# USB_PROGRAMMER.net
KiCad netlist of a schematic drawn in Altium Designer
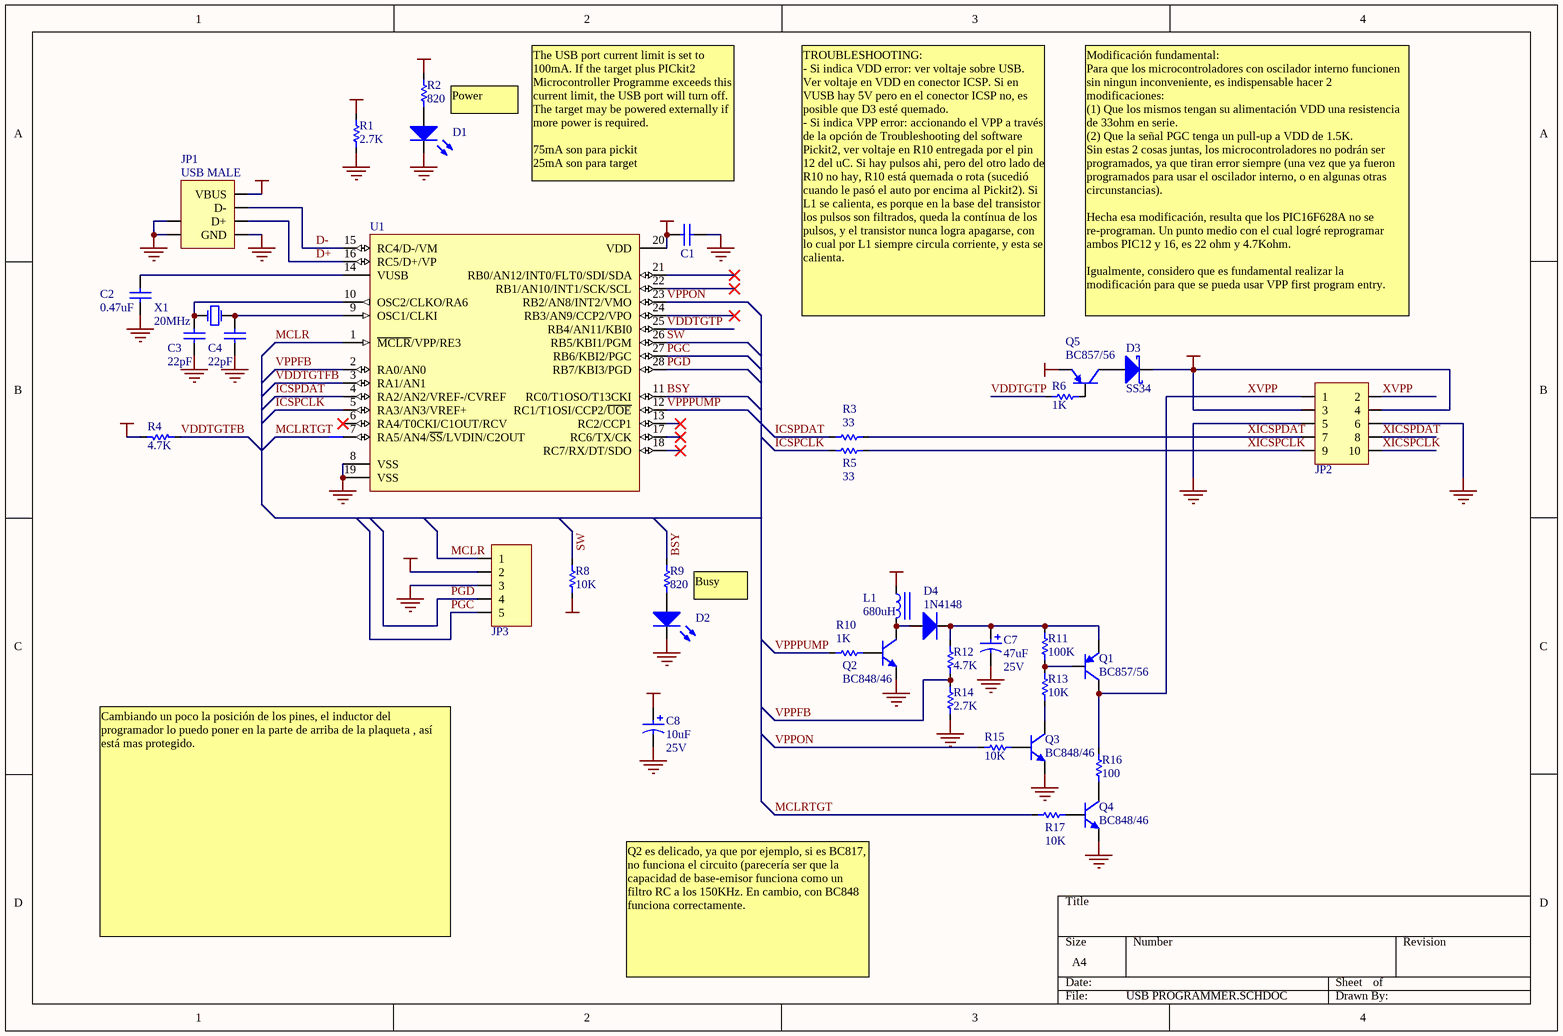
[diagram p0: USB PROGRAMMER.SCHDOC]

(export (version "E")
  (design (tool "Eeschema 10.0.6"))
  (components
    (comp (ref "C1")
      (value "Cap")
      (footprint "1206NP")
      (description "Capacitor")
      (fields (field (name "VOLTAGE") "50V"))
      (libsource (lib "FEDE") (part "Cap"))
    )
    (comp (ref "C2")
      (value "0.47uF")
      (footprint "1206NP")
      (description "Capacitor")
      (fields (field (name "VOLTAGE") "50V") (field (name "Comment") "Cap"))
      (libsource (lib "FEDE") (part "Cap"))
    )
    (comp (ref "C3")
      (value "22pF")
      (footprint "1206NP")
      (description "Capacitor")
      (fields (field (name "VOLTAGE") "50V") (field (name "Comment") "Cap"))
      (libsource (lib "FEDE") (part "Cap"))
    )
    (comp (ref "C4")
      (value "22pF")
      (footprint "1206NP")
      (description "Capacitor")
      (fields (field (name "VOLTAGE") "50V") (field (name "Comment") "Cap"))
      (libsource (lib "FEDE") (part "Cap"))
    )
    (comp (ref "C7")
      (value "47uF")
      (footprint "cap4mm")
      (description "Capacitor Polarizado")
      (fields (field (name "VOLTAJE") "25V") (field (name "Comment") "Cap Pol"))
      (libsource (lib "FEDE") (part "Cap Pol"))
    )
    (comp (ref "C8")
      (value "10uF")
      (footprint "cap4mm")
      (description "Capacitor Polarizado")
      (fields (field (name "VOLTAJE") "25V") (field (name "Comment") "Cap Pol"))
      (libsource (lib "FEDE") (part "Cap Pol"))
    )
    (comp (ref "D1")
      (value "LED")
      (footprint "LED3mm")
      (description "Led")
      (libsource (lib "FEDE") (part "LED"))
    )
    (comp (ref "D2")
      (value "LED")
      (footprint "LED3mm")
      (description "Led")
      (libsource (lib "FEDE") (part "LED"))
    )
    (comp (ref "D3")
      (value "SS34")
      (footprint "diode600")
      (description "Schottky Diode 3A 40V")
      (libsource (lib "FEDE") (part "1N5822"))
    )
    (comp (ref "D4")
      (value "1N4148")
      (footprint "DSMD1MM")
      (description "High Conductance Fast Diode")
      (libsource (lib "FEDE") (part "1N4148"))
    )
    (comp (ref "JP1")
      (value "USB MALE")
      (footprint "USB_A_MALE")
      (description "USB Connector")
      (libsource (lib "FEDE") (part "USB"))
    )
    (comp (ref "JP2")
      (value "Header5x1")
      (footprint "IDC5x2_90")
      (description "Header 5x2")
      (libsource (lib "FEDE") (part "Header5x2"))
    )
    (comp (ref "JP3")
      (value "Header5x1")
      (footprint "HDR5x1")
      (description "Header 5x1")
      (libsource (lib "FEDE") (part "Header5x1"))
    )
    (comp (ref "L1")
      (value "680uH")
      (footprint "RES400TH")
      (description "Inductor")
      (libsource (lib "FEDE") (part "Inductor"))
    )
    (comp (ref "Q1")
      (value "BC857/56")
      (footprint "SOT23")
      (description "100mA 65V PNP Bipolar Transistor")
      (libsource (lib "FEDE") (part "BC856A"))
    )
    (comp (ref "Q2")
      (value "BC848/46")
      (footprint "SOT23")
      (description "100mA 65V NPN Bipolar Transistor")
      (libsource (lib "FEDE") (part "BC846A"))
    )
    (comp (ref "Q3")
      (value "BC848/46")
      (footprint "SOT23")
      (description "100mA 65V NPN Bipolar Transistor")
      (libsource (lib "FEDE") (part "BC846A"))
    )
    (comp (ref "Q4")
      (value "BC848/46")
      (footprint "SOT23")
      (description "100mA 65V NPN Bipolar Transistor")
      (libsource (lib "FEDE") (part "BC846A"))
    )
    (comp (ref "Q5")
      (value "BC857/56")
      (footprint "SOT23")
      (description "100mA 65V PNP Bipolar Transistor")
      (libsource (lib "FEDE") (part "BC856A"))
    )
    (comp (ref "R1")
      (value "2.7K")
      (footprint "1206NP")
      (description "Resistor")
      (fields (field (name "POWER") "0.25W") (field (name "Comment") "Res"))
      (libsource (lib "FEDE") (part "Res"))
    )
    (comp (ref "R2")
      (value "820")
      (footprint "1206NP")
      (description "Resistor")
      (fields (field (name "POWER") "0.25W") (field (name "Comment") "Res"))
      (libsource (lib "FEDE") (part "Res"))
    )
    (comp (ref "R3")
      (value "33")
      (footprint "1206NP")
      (description "Resistor")
      (fields (field (name "POWER") "0.25W") (field (name "Comment") "Res"))
      (libsource (lib "FEDE") (part "Res"))
    )
    (comp (ref "R4")
      (value "4.7K")
      (footprint "1206NP")
      (description "Resistor")
      (fields (field (name "POWER") "0.25W") (field (name "Comment") "Res"))
      (libsource (lib "FEDE") (part "Res"))
    )
    (comp (ref "R5")
      (value "33")
      (footprint "1206NP")
      (description "Resistor")
      (fields (field (name "POWER") "0.25W") (field (name "Comment") "Res"))
      (libsource (lib "FEDE") (part "Res"))
    )
    (comp (ref "R6")
      (value "1K")
      (footprint "res250th_vertical")
      (description "Resistor")
      (fields (field (name "POWER") "0.25W") (field (name "Comment") "Res"))
      (libsource (lib "FEDE") (part "Res"))
    )
    (comp (ref "R8")
      (value "10K")
      (footprint "1206NP")
      (description "Resistor")
      (fields (field (name "POWER") "0.25W") (field (name "Comment") "Res"))
      (libsource (lib "FEDE") (part "Res"))
    )
    (comp (ref "R9")
      (value "820")
      (footprint "1206NP")
      (description "Resistor")
      (fields (field (name "POWER") "0.25W") (field (name "Comment") "Res"))
      (libsource (lib "FEDE") (part "Res"))
    )
    (comp (ref "R10")
      (value "1K")
      (footprint "1206NP")
      (description "Resistor")
      (fields (field (name "POWER") "0.25W") (field (name "Comment") "Res"))
      (libsource (lib "FEDE") (part "Res"))
    )
    (comp (ref "R11")
      (value "100K")
      (footprint "1206NP")
      (description "Resistor")
      (fields (field (name "POWER") "0.25W") (field (name "Comment") "Res"))
      (libsource (lib "FEDE") (part "Res"))
    )
    (comp (ref "R12")
      (value "4.7K")
      (footprint "1206NP")
      (description "Resistor")
      (fields (field (name "POWER") "0.25W") (field (name "Comment") "Res"))
      (libsource (lib "FEDE") (part "Res"))
    )
    (comp (ref "R13")
      (value "10K")
      (footprint "1206NP")
      (description "Resistor")
      (fields (field (name "POWER") "0.25W") (field (name "Comment") "Res"))
      (libsource (lib "FEDE") (part "Res"))
    )
    (comp (ref "R14")
      (value "2.7K")
      (footprint "1206NP")
      (description "Resistor")
      (fields (field (name "POWER") "0.25W") (field (name "Comment") "Res"))
      (libsource (lib "FEDE") (part "Res"))
    )
    (comp (ref "R15")
      (value "10K")
      (footprint "1206NP")
      (description "Resistor")
      (fields (field (name "POWER") "0.25W") (field (name "Comment") "Res"))
      (libsource (lib "FEDE") (part "Res"))
    )
    (comp (ref "R16")
      (value "100")
      (footprint "1206NP")
      (description "Resistor")
      (fields (field (name "POWER") "0.25W") (field (name "Comment") "Res"))
      (libsource (lib "FEDE") (part "Res"))
    )
    (comp (ref "R17")
      (value "10K")
      (footprint "RES250TH")
      (description "Resistor")
      (fields (field (name "POWER") "0.25W") (field (name "Comment") "Res"))
      (libsource (lib "FEDE") (part "Res"))
    )
    (comp (ref "U1")
      (value "~")
      (footprint "soic28")
      (description "Enhanced FLASH Microcontroller")
      (libsource (lib "FEDE") (part "PIC18F2550"))
    )
    (comp (ref "W1")
      (value "CABLE")
      (footprint "1206NP")
      (description "Cable")
      (libsource (lib "FEDE") (part "CABLE"))
    )
    (comp (ref "X1")
      (value "20MHz")
      (footprint "XTAL1")
      (description "Crystal Oscillator")
      (fields (field (name "Comment") "XTAL"))
      (libsource (lib "FEDE") (part "XTAL"))
    )
  )
  (nets
    (net (code "1") (name "/BSY") (class "Default")
      (node (ref "R9") (pin "2") (pinfunction "2_2") (pintype "passive"))
      (node (ref "U1") (pin "11") (pinfunction "RC0/T1OSO/T13CKI_11") (pintype "bidirectional"))
    )
    (net (code "2") (name "/D+") (class "Default")
      (node (ref "JP1") (pin "3") (pinfunction "D+_3") (pintype "passive"))
      (node (ref "U1") (pin "16") (pinfunction "RC5/D+/VP_16") (pintype "bidirectional"))
    )
    (net (code "3") (name "/D-") (class "Default")
      (node (ref "JP1") (pin "2") (pinfunction "D-_2") (pintype "passive"))
      (node (ref "U1") (pin "15") (pinfunction "RC4/D-/VM_15") (pintype "bidirectional"))
    )
    (net (code "4") (name "/ICSPCLK") (class "Default")
      (node (ref "R5") (pin "1") (pinfunction "1_1") (pintype "passive"))
      (node (ref "U1") (pin "5") (pinfunction "RA3/AN3/VREF+_5") (pintype "bidirectional"))
    )
    (net (code "5") (name "/ICSPDAT") (class "Default")
      (node (ref "R3") (pin "1") (pinfunction "1_1") (pintype "passive"))
      (node (ref "U1") (pin "4") (pinfunction "RA2/AN2/VREF-/CVREF_4") (pintype "bidirectional"))
    )
    (net (code "6") (name "/MCLR") (class "Default")
      (node (ref "JP3") (pin "1") (pinfunction "1_1") (pintype "passive"))
      (node (ref "U1") (pin "1") (pinfunction "~{MCLR}/VPP/RE3_1") (pintype "input"))
    )
    (net (code "7") (name "/MCLRTGT") (class "Default")
      (node (ref "R17") (pin "2") (pinfunction "2_2") (pintype "passive"))
      (node (ref "W1") (pin "2") (pinfunction "2_2") (pintype "passive"))
    )
    (net (code "8") (name "/PGC") (class "Default")
      (node (ref "JP3") (pin "5") (pinfunction "5_5") (pintype "passive"))
      (node (ref "U1") (pin "27") (pinfunction "RB6/KBI2/PGC_27") (pintype "bidirectional"))
    )
    (net (code "9") (name "/PGD") (class "Default")
      (node (ref "JP3") (pin "4") (pinfunction "4_4") (pintype "passive"))
      (node (ref "U1") (pin "28") (pinfunction "RB7/KBI3/PGD_28") (pintype "bidirectional"))
    )
    (net (code "10") (name "/SW") (class "Default")
      (node (ref "R8") (pin "1") (pinfunction "1_1") (pintype "passive"))
      (node (ref "U1") (pin "26") (pinfunction "RB5/KBI1/PGM_26") (pintype "bidirectional"))
    )
    (net (code "11") (name "/VDDTGTFB") (class "Default")
      (node (ref "R4") (pin "1") (pinfunction "1_1") (pintype "passive"))
      (node (ref "U1") (pin "3") (pinfunction "RA1/AN1_3") (pintype "bidirectional"))
    )
    (net (code "12") (name "/VDDTGTP") (class "Default")
      (node (ref "R6") (pin "2") (pinfunction "2_2") (pintype "passive"))
      (node (ref "U1") (pin "25") (pinfunction "RB4/AN11/KBI0_25") (pintype "bidirectional"))
    )
    (net (code "13") (name "/VPPFB") (class "Default")
      (node (ref "R12") (pin "1") (pinfunction "1_1") (pintype "passive"))
      (node (ref "R14") (pin "2") (pinfunction "2_2") (pintype "passive"))
      (node (ref "U1") (pin "2") (pinfunction "RA0/AN0_2") (pintype "bidirectional"))
    )
    (net (code "14") (name "/VPPON") (class "Default")
      (node (ref "R15") (pin "2") (pinfunction "2_2") (pintype "passive"))
      (node (ref "U1") (pin "23") (pinfunction "RB2/AN8/INT2/VMO_23") (pintype "bidirectional"))
    )
    (net (code "15") (name "/VPPPUMP") (class "Default")
      (node (ref "R10") (pin "2") (pinfunction "2_2") (pintype "passive"))
      (node (ref "U1") (pin "12") (pinfunction "RC1/T1OSI/CCP2/~{UOE}_12") (pintype "bidirectional"))
    )
    (net (code "16") (name "/XICSPCLK") (class "Default")
      (node (ref "JP2") (pin "10") (pinfunction "10_10") (pintype "passive"))
      (node (ref "JP2") (pin "9") (pinfunction "9_9") (pintype "passive"))
      (node (ref "R5") (pin "2") (pinfunction "2_2") (pintype "passive"))
    )
    (net (code "17") (name "/XICSPDAT") (class "Default")
      (node (ref "JP2") (pin "7") (pinfunction "7_7") (pintype "passive"))
      (node (ref "JP2") (pin "8") (pinfunction "8_8") (pintype "passive"))
      (node (ref "R3") (pin "2") (pinfunction "2_2") (pintype "passive"))
    )
    (net (code "18") (name "/XVPP") (class "Default")
      (node (ref "JP2") (pin "1") (pinfunction "1_1") (pintype "passive"))
      (node (ref "JP2") (pin "2") (pinfunction "2_2") (pintype "passive"))
      (node (ref "Q1") (pin "1") (pinfunction "C_1") (pintype "passive"))
      (node (ref "R16") (pin "2") (pinfunction "2_2") (pintype "passive"))
    )
    (net (code "19") (name "GND") (class "Default")
      (node (ref "C1") (pin "1") (pinfunction "1_1") (pintype "passive"))
      (node (ref "C2") (pin "1") (pinfunction "1_1") (pintype "passive"))
      (node (ref "C3") (pin "1") (pinfunction "1_1") (pintype "passive"))
      (node (ref "C4") (pin "2") (pinfunction "2_2") (pintype "passive"))
      (node (ref "C7") (pin "2") (pinfunction "2_2") (pintype "passive"))
      (node (ref "C8") (pin "2") (pinfunction "2_2") (pintype "passive"))
      (node (ref "D1") (pin "2") (pinfunction "K_2") (pintype "passive"))
      (node (ref "D2") (pin "2") (pinfunction "K_2") (pintype "passive"))
      (node (ref "JP1") (pin "4") (pinfunction "GND_4") (pintype "passive"))
      (node (ref "JP1") (pin "5") (pintype "passive"))
      (node (ref "JP1") (pin "6") (pintype "passive"))
      (node (ref "JP2") (pin "5") (pinfunction "5_5") (pintype "passive"))
      (node (ref "JP2") (pin "6") (pinfunction "6_6") (pintype "passive"))
      (node (ref "JP3") (pin "3") (pinfunction "3_3") (pintype "passive"))
      (node (ref "Q2") (pin "3") (pinfunction "E_3") (pintype "passive"))
      (node (ref "Q3") (pin "3") (pinfunction "E_3") (pintype "passive"))
      (node (ref "Q4") (pin "3") (pinfunction "E_3") (pintype "passive"))
      (node (ref "R1") (pin "2") (pinfunction "2_2") (pintype "passive"))
      (node (ref "R14") (pin "1") (pinfunction "1_1") (pintype "passive"))
      (node (ref "U1") (pin "19") (pinfunction "VSS_19") (pintype "power_in"))
      (node (ref "U1") (pin "8") (pinfunction "VSS_8") (pintype "power_in"))
    )
    (net (code "20") (name "Net-(D1-A)") (class "Default")
      (node (ref "D1") (pin "1") (pinfunction "A_1") (pintype "passive"))
      (node (ref "R2") (pin "1") (pinfunction "1_1") (pintype "passive"))
    )
    (net (code "21") (name "Net-(D2-A)") (class "Default")
      (node (ref "D2") (pin "1") (pinfunction "A_1") (pintype "passive"))
      (node (ref "R9") (pin "1") (pinfunction "1_1") (pintype "passive"))
    )
    (net (code "22") (name "Net-(D3-A)") (class "Default")
      (node (ref "D3") (pin "1") (pinfunction "A_1") (pintype "passive"))
      (node (ref "Q5") (pin "1") (pinfunction "C_1") (pintype "passive"))
    )
    (net (code "23") (name "Net-(Q1-B)") (class "Default")
      (node (ref "Q1") (pin "2") (pinfunction "B_2") (pintype "passive"))
      (node (ref "R11") (pin "1") (pinfunction "1_1") (pintype "passive"))
      (node (ref "R13") (pin "2") (pinfunction "2_2") (pintype "passive"))
    )
    (net (code "24") (name "Net-(Q1-E)") (class "Default")
      (node (ref "C7") (pin "1") (pinfunction "1_1") (pintype "passive"))
      (node (ref "D4") (pin "2") (pinfunction "2_2") (pintype "passive"))
      (node (ref "Q1") (pin "3") (pinfunction "E_3") (pintype "passive"))
      (node (ref "R11") (pin "2") (pinfunction "2_2") (pintype "passive"))
      (node (ref "R12") (pin "2") (pinfunction "2_2") (pintype "passive"))
    )
    (net (code "25") (name "Net-(Q2-B)") (class "Default")
      (node (ref "Q2") (pin "2") (pinfunction "B_2") (pintype "passive"))
      (node (ref "R10") (pin "1") (pinfunction "1_1") (pintype "passive"))
    )
    (net (code "26") (name "Net-(Q2-C)") (class "Default")
      (node (ref "D4") (pin "1") (pinfunction "1_1") (pintype "passive"))
      (node (ref "L1") (pin "2") (pinfunction "2_2") (pintype "passive"))
      (node (ref "Q2") (pin "1") (pinfunction "C_1") (pintype "passive"))
    )
    (net (code "27") (name "Net-(Q3-B)") (class "Default")
      (node (ref "Q3") (pin "2") (pinfunction "B_2") (pintype "passive"))
      (node (ref "R15") (pin "1") (pinfunction "1_1") (pintype "passive"))
    )
    (net (code "28") (name "Net-(Q3-C)") (class "Default")
      (node (ref "Q3") (pin "1") (pinfunction "C_1") (pintype "passive"))
      (node (ref "R13") (pin "1") (pinfunction "1_1") (pintype "passive"))
    )
    (net (code "29") (name "Net-(Q4-B)") (class "Default")
      (node (ref "Q4") (pin "2") (pinfunction "B_2") (pintype "passive"))
      (node (ref "R17") (pin "1") (pinfunction "1_1") (pintype "passive"))
    )
    (net (code "30") (name "Net-(Q4-C)") (class "Default")
      (node (ref "Q4") (pin "1") (pinfunction "C_1") (pintype "passive"))
      (node (ref "R16") (pin "1") (pinfunction "1_1") (pintype "passive"))
    )
    (net (code "31") (name "Net-(Q5-B)") (class "Default")
      (node (ref "Q5") (pin "2") (pinfunction "B_2") (pintype "passive"))
      (node (ref "R6") (pin "1") (pinfunction "1_1") (pintype "passive"))
    )
    (net (code "32") (name "Net-(U1-OSC1{slash}CLKI)") (class "Default")
      (node (ref "C4") (pin "1") (pinfunction "1_1") (pintype "passive"))
      (node (ref "U1") (pin "9") (pinfunction "OSC1/CLKI_9") (pintype "input"))
      (node (ref "X1") (pin "2") (pinfunction "OSC2_2") (pintype "passive"))
    )
    (net (code "33") (name "Net-(U1-OSC2{slash}CLKO{slash}RA6)") (class "Default")
      (node (ref "C3") (pin "2") (pinfunction "2_2") (pintype "passive"))
      (node (ref "U1") (pin "10") (pinfunction "OSC2/CLKO/RA6_10") (pintype "output"))
      (node (ref "X1") (pin "1") (pinfunction "OSC1_1") (pintype "passive"))
    )
    (net (code "34") (name "Net-(U1-RA5{slash}AN4{slash}~{SS}{slash}LVDIN{slash}C2OUT)") (class "Default")
      (node (ref "U1") (pin "7") (pinfunction "RA5/AN4/~{SS}/LVDIN/C2OUT_7") (pintype "bidirectional"))
      (node (ref "W1") (pin "1") (pinfunction "1_1") (pintype "passive"))
    )
    (net (code "35") (name "Net-(U1-VUSB)") (class "Default")
      (node (ref "C2") (pin "2") (pinfunction "2_2") (pintype "passive"))
      (node (ref "U1") (pin "14") (pinfunction "VUSB_14") (pintype "passive"))
    )
    (net (code "36") (name "VCC") (class "Default")
      (node (ref "C1") (pin "2") (pinfunction "2_2") (pintype "passive"))
      (node (ref "C8") (pin "1") (pinfunction "1_1") (pintype "passive"))
      (node (ref "JP1") (pin "1") (pinfunction "VBUS_1") (pintype "passive"))
      (node (ref "JP3") (pin "2") (pinfunction "2_2") (pintype "passive"))
      (node (ref "L1") (pin "1") (pinfunction "1_1") (pintype "passive"))
      (node (ref "Q5") (pin "3") (pinfunction "E_3") (pintype "passive"))
      (node (ref "R1") (pin "1") (pinfunction "1_1") (pintype "passive"))
      (node (ref "R2") (pin "2") (pinfunction "2_2") (pintype "passive"))
      (node (ref "R8") (pin "2") (pinfunction "2_2") (pintype "passive"))
      (node (ref "U1") (pin "20") (pinfunction "VDD_20") (pintype "power_in"))
    )
    (net (code "37") (name "VDDTGT") (class "Default")
      (node (ref "D3") (pin "2") (pinfunction "K_2") (pintype "passive"))
      (node (ref "JP2") (pin "3") (pinfunction "3_3") (pintype "passive"))
      (node (ref "JP2") (pin "4") (pinfunction "4_4") (pintype "passive"))
      (node (ref "R4") (pin "2") (pinfunction "2_2") (pintype "passive"))
    )
    (net (code "38") (name "unconnected-(U1-RA4{slash}T0CKI{slash}C1OUT{slash}RCV-Pad6)") (class "Default")
      (node (ref "U1") (pin "6") (pinfunction "RA4/T0CKI/C1OUT/RCV_6") (pintype "bidirectional+no_connect"))
    )
    (net (code "39") (name "unconnected-(U1-RB0{slash}AN12{slash}INT0{slash}FLT0{slash}SDI{slash}SDA-Pad21)") (class "Default")
      (node (ref "U1") (pin "21") (pinfunction "RB0/AN12/INT0/FLT0/SDI/SDA_21") (pintype "bidirectional+no_connect"))
    )
    (net (code "40") (name "unconnected-(U1-RB1{slash}AN10{slash}INT1{slash}SCK{slash}SCL-Pad22)") (class "Default")
      (node (ref "U1") (pin "22") (pinfunction "RB1/AN10/INT1/SCK/SCL_22") (pintype "bidirectional+no_connect"))
    )
    (net (code "41") (name "unconnected-(U1-RB3{slash}AN9{slash}CCP2{slash}VPO-Pad24)") (class "Default")
      (node (ref "U1") (pin "24") (pinfunction "RB3/AN9/CCP2/VPO_24") (pintype "bidirectional+no_connect"))
    )
    (net (code "42") (name "unconnected-(U1-RC2{slash}CCP1-Pad13)") (class "Default")
      (node (ref "U1") (pin "13") (pinfunction "RC2/CCP1_13") (pintype "bidirectional+no_connect"))
    )
    (net (code "43") (name "unconnected-(U1-RC6{slash}TX{slash}CK-Pad17)") (class "Default")
      (node (ref "U1") (pin "17") (pinfunction "RC6/TX/CK_17") (pintype "bidirectional+no_connect"))
    )
    (net (code "44") (name "unconnected-(U1-RC7{slash}RX{slash}DT{slash}SDO-Pad18)") (class "Default")
      (node (ref "U1") (pin "18") (pinfunction "RC7/RX/DT/SDO_18") (pintype "bidirectional+no_connect"))
    )
  )
)
